# CubeNode.net
KiCad netlist of a schematic drawn in Altium Designer
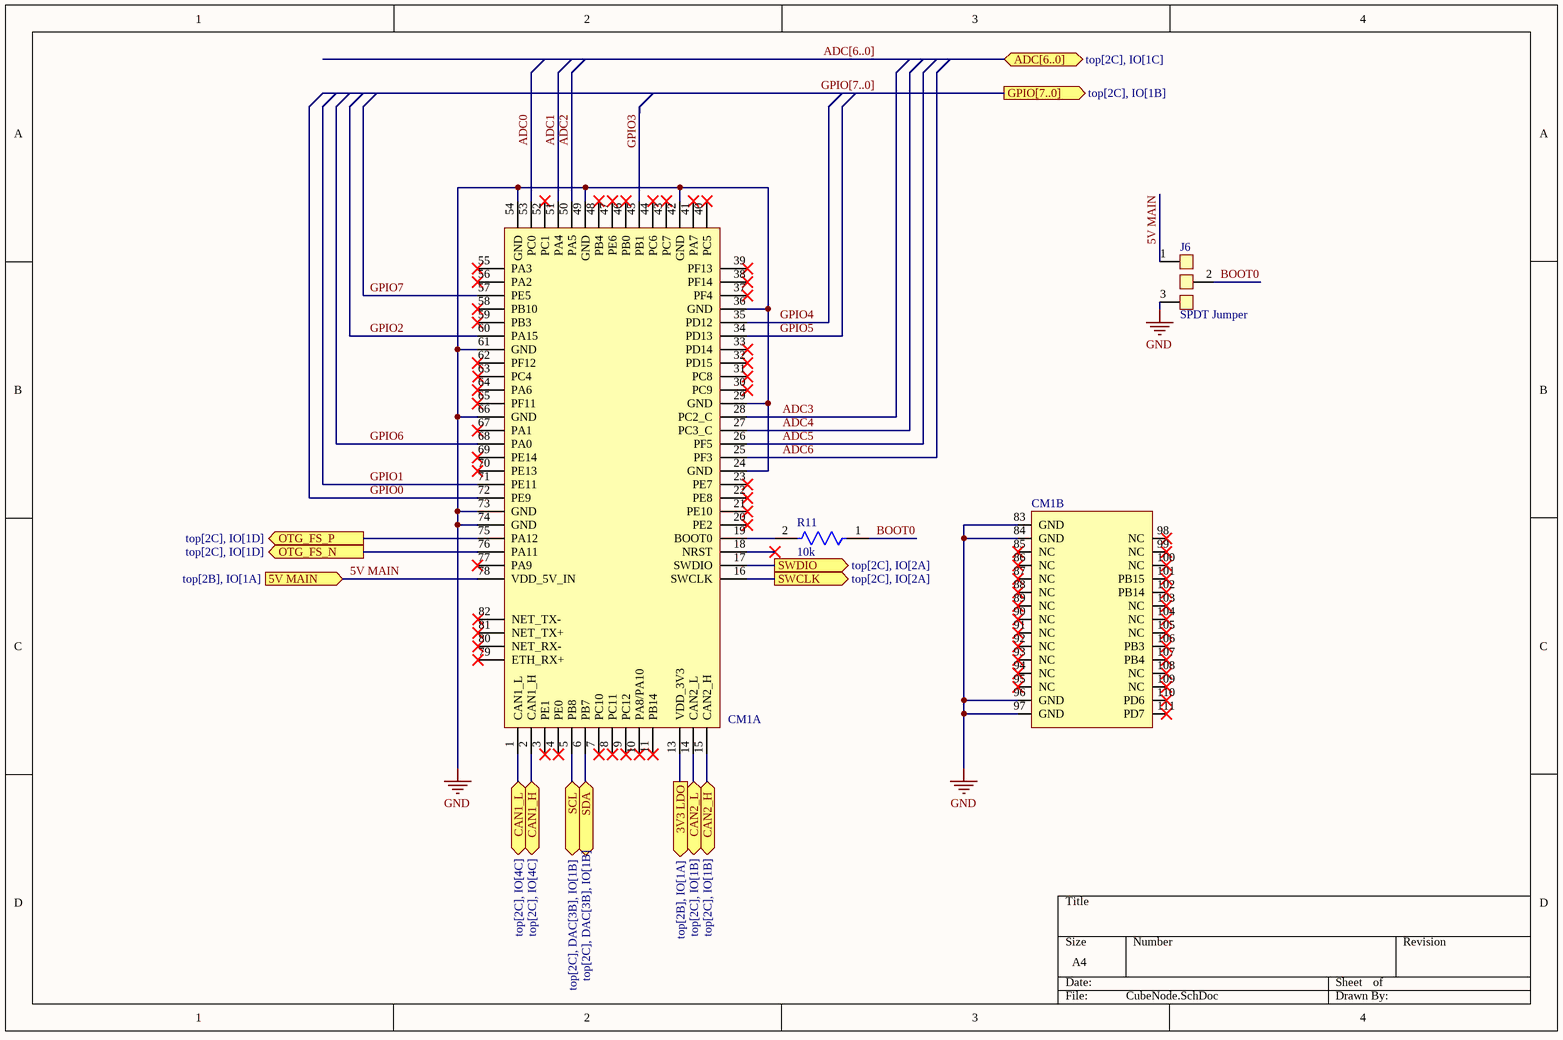
[diagram p0: CubeNode.SchDoc]

(export (version "E")
  (design (tool "Eeschema 10.0.6"))
  (components
    (comp (ref "CM1")
      (value "CUBENODE_FOOTPRINT")
      (footprint "CubeNode Footprint:CubeNode")
      (libsource (lib "CubeNode Footprint") (part "CubeNode Footprint"))
    )
    (comp (ref "J6")
      (value "SPDT Jumper")
      (footprint "SPDT Jumper")
      (libsource (lib "jumpers") (part "SPDT Jumper"))
    )
    (comp (ref "R11")
      (value "10k")
      (footprint "FP-AF0603-MFG")
      (description "Anti-Sulfurated Chip Resistors Automotive Grade 10kΩ 1% 100ppm/°C 0603")
      (libsource (lib "Altium Content Vault") (part "1029c3af85768c4190bb7ad29bc67b5"))
    )
  )
  (nets
    (net (code "1") (name "/3V3 LDO") (class "Default")
      (node (ref "CM1") (pin "13") (pinfunction "VDD_3V3_13") (pintype "passive"))
    )
    (net (code "2") (name "/5V MAIN") (class "Default")
      (node (ref "CM1") (pin "78") (pinfunction "VDD_5V_IN_78") (pintype "passive"))
      (node (ref "J6") (pin "1") (pinfunction "1_1") (pintype "passive"))
    )
    (net (code "3") (name "/ADC0") (class "Default")
      (node (ref "CM1") (pin "53") (pinfunction "PC0_53") (pintype "passive"))
    )
    (net (code "4") (name "/ADC1") (class "Default")
      (node (ref "CM1") (pin "51") (pinfunction "PA4_51") (pintype "passive"))
    )
    (net (code "5") (name "/ADC2") (class "Default")
      (node (ref "CM1") (pin "50") (pinfunction "PA5_50") (pintype "passive"))
    )
    (net (code "6") (name "/ADC3") (class "Default")
      (node (ref "CM1") (pin "28") (pinfunction "PC2_C_28") (pintype "passive"))
    )
    (net (code "7") (name "/ADC4") (class "Default")
      (node (ref "CM1") (pin "27") (pinfunction "PC3_C_27") (pintype "passive"))
    )
    (net (code "8") (name "/ADC5") (class "Default")
      (node (ref "CM1") (pin "26") (pinfunction "PF5_26") (pintype "passive"))
    )
    (net (code "9") (name "/ADC6") (class "Default")
      (node (ref "CM1") (pin "25") (pinfunction "PF3_25") (pintype "passive"))
    )
    (net (code "11") (name "/BOOT0") (class "Default")
      (node (ref "J6") (pin "2") (pinfunction "2_2") (pintype "passive"))
      (node (ref "R11") (pin "1") (pinfunction "1_1") (pintype "passive"))
    )
    (net (code "12") (name "/CAN1_H") (class "Default")
      (node (ref "CM1") (pin "2") (pinfunction "CAN1_H_2") (pintype "passive"))
    )
    (net (code "13") (name "/CAN1_L") (class "Default")
      (node (ref "CM1") (pin "1") (pinfunction "CAN1_L_1") (pintype "passive"))
    )
    (net (code "14") (name "/CAN2_H") (class "Default")
      (node (ref "CM1") (pin "15") (pinfunction "CAN2_H_15") (pintype "passive"))
    )
    (net (code "15") (name "/CAN2_L") (class "Default")
      (node (ref "CM1") (pin "14") (pinfunction "CAN2_L_14") (pintype "passive"))
    )
    (net (code "16") (name "/GPIO0") (class "Default")
      (node (ref "CM1") (pin "72") (pinfunction "PE9_72") (pintype "passive"))
    )
    (net (code "17") (name "/GPIO1") (class "Default")
      (node (ref "CM1") (pin "71") (pinfunction "PE11_71") (pintype "passive"))
    )
    (net (code "18") (name "/GPIO2") (class "Default")
      (node (ref "CM1") (pin "60") (pinfunction "PA15_60") (pintype "passive"))
    )
    (net (code "19") (name "/GPIO3") (class "Default")
      (node (ref "CM1") (pin "45") (pinfunction "PB1_45") (pintype "passive"))
    )
    (net (code "20") (name "/GPIO4") (class "Default")
      (node (ref "CM1") (pin "35") (pinfunction "PD12_35") (pintype "passive"))
    )
    (net (code "21") (name "/GPIO5") (class "Default")
      (node (ref "CM1") (pin "34") (pinfunction "PD13_34") (pintype "passive"))
    )
    (net (code "22") (name "/GPIO6") (class "Default")
      (node (ref "CM1") (pin "68") (pinfunction "PA0_68") (pintype "passive"))
    )
    (net (code "23") (name "/GPIO7") (class "Default")
      (node (ref "CM1") (pin "57") (pinfunction "PE5_57") (pintype "passive"))
    )
    (net (code "25") (name "/OTG_FS_N") (class "Default")
      (node (ref "CM1") (pin "76") (pinfunction "PA11_76") (pintype "passive"))
    )
    (net (code "26") (name "/OTG_FS_P") (class "Default")
      (node (ref "CM1") (pin "75") (pinfunction "PA12_75") (pintype "passive"))
    )
    (net (code "27") (name "/SCL") (class "Default")
      (node (ref "CM1") (pin "5") (pinfunction "PB8_5") (pintype "passive"))
    )
    (net (code "28") (name "/SDA") (class "Default")
      (node (ref "CM1") (pin "6") (pinfunction "PB7_6") (pintype "passive"))
    )
    (net (code "29") (name "/SWCLK") (class "Default")
      (node (ref "CM1") (pin "16") (pinfunction "SWCLK_16") (pintype "passive"))
    )
    (net (code "30") (name "/SWDIO") (class "Default")
      (node (ref "CM1") (pin "17") (pinfunction "SWDIO_17") (pintype "passive"))
    )
    (net (code "31") (name "GND") (class "Default")
      (node (ref "CM1") (pin "24") (pinfunction "GND_24") (pintype "passive"))
      (node (ref "CM1") (pin "29") (pinfunction "GND_29") (pintype "passive"))
      (node (ref "CM1") (pin "36") (pinfunction "GND_36") (pintype "passive"))
      (node (ref "CM1") (pin "42") (pinfunction "GND_42") (pintype "passive"))
      (node (ref "CM1") (pin "49") (pinfunction "GND_49") (pintype "passive"))
      (node (ref "CM1") (pin "54") (pinfunction "GND_54") (pintype "passive"))
      (node (ref "CM1") (pin "61") (pinfunction "GND_61") (pintype "passive"))
      (node (ref "CM1") (pin "66") (pinfunction "GND_66") (pintype "passive"))
      (node (ref "CM1") (pin "73") (pinfunction "GND_73") (pintype "passive"))
      (node (ref "CM1") (pin "74") (pinfunction "GND_74") (pintype "passive"))
      (node (ref "CM1") (pin "83") (pinfunction "GND_83") (pintype "passive"))
      (node (ref "CM1") (pin "84") (pinfunction "GND_84") (pintype "passive"))
      (node (ref "CM1") (pin "96") (pinfunction "GND_96") (pintype "passive"))
      (node (ref "CM1") (pin "97") (pinfunction "GND_97") (pintype "passive"))
      (node (ref "J6") (pin "3") (pinfunction "3_3") (pintype "passive"))
    )
    (net (code "32") (name "Net-(CM1A-BOOT0)") (class "Default")
      (node (ref "CM1") (pin "19") (pinfunction "BOOT0_19") (pintype "passive"))
      (node (ref "R11") (pin "2") (pinfunction "2_2") (pintype "passive"))
    )
    (net (code "33") (name "unconnected-(CM1A-ETH_RX+-Pad79)") (class "Default")
      (node (ref "CM1") (pin "79") (pinfunction "ETH_RX+_79") (pintype "passive+no_connect"))
    )
    (net (code "34") (name "unconnected-(CM1A-NET_RX--Pad80)") (class "Default")
      (node (ref "CM1") (pin "80") (pinfunction "NET_RX-_80") (pintype "passive+no_connect"))
    )
    (net (code "35") (name "unconnected-(CM1A-NET_TX+-Pad81)") (class "Default")
      (node (ref "CM1") (pin "81") (pinfunction "NET_TX+_81") (pintype "passive+no_connect"))
    )
    (net (code "36") (name "unconnected-(CM1A-NET_TX--Pad82)") (class "Default")
      (node (ref "CM1") (pin "82") (pinfunction "NET_TX-_82") (pintype "passive+no_connect"))
    )
    (net (code "37") (name "unconnected-(CM1A-NRST-Pad18)") (class "Default")
      (node (ref "CM1") (pin "18") (pinfunction "NRST_18") (pintype "passive+no_connect"))
    )
    (net (code "38") (name "unconnected-(CM1A-PA1-Pad67)") (class "Default")
      (node (ref "CM1") (pin "67") (pinfunction "PA1_67") (pintype "passive+no_connect"))
    )
    (net (code "39") (name "unconnected-(CM1A-PA2-Pad56)") (class "Default")
      (node (ref "CM1") (pin "56") (pinfunction "PA2_56") (pintype "passive+no_connect"))
    )
    (net (code "40") (name "unconnected-(CM1A-PA3-Pad55)") (class "Default")
      (node (ref "CM1") (pin "55") (pinfunction "PA3_55") (pintype "passive+no_connect"))
    )
    (net (code "41") (name "unconnected-(CM1A-PA6-Pad64)") (class "Default")
      (node (ref "CM1") (pin "64") (pinfunction "PA6_64") (pintype "passive+no_connect"))
    )
    (net (code "42") (name "unconnected-(CM1A-PA7-Pad41)") (class "Default")
      (node (ref "CM1") (pin "41") (pinfunction "PA7_41") (pintype "passive+no_connect"))
    )
    (net (code "43") (name "unconnected-(CM1A-PA8{slash}PA10-Pad10)") (class "Default")
      (node (ref "CM1") (pin "10") (pinfunction "PA8/PA10_10") (pintype "passive+no_connect"))
    )
    (net (code "44") (name "unconnected-(CM1A-PA9-Pad77)") (class "Default")
      (node (ref "CM1") (pin "77") (pinfunction "PA9_77") (pintype "passive+no_connect"))
    )
    (net (code "45") (name "unconnected-(CM1A-PB0-Pad46)") (class "Default")
      (node (ref "CM1") (pin "46") (pinfunction "PB0_46") (pintype "passive+no_connect"))
    )
    (net (code "46") (name "unconnected-(CM1A-PB3-Pad59)") (class "Default")
      (node (ref "CM1") (pin "59") (pinfunction "PB3_59") (pintype "passive+no_connect"))
    )
    (net (code "47") (name "unconnected-(CM1A-PB4-Pad48)") (class "Default")
      (node (ref "CM1") (pin "48") (pinfunction "PB4_48") (pintype "passive+no_connect"))
    )
    (net (code "48") (name "unconnected-(CM1A-PB10-Pad58)") (class "Default")
      (node (ref "CM1") (pin "58") (pinfunction "PB10_58") (pintype "passive+no_connect"))
    )
    (net (code "49") (name "unconnected-(CM1A-PB14-Pad11)") (class "Default")
      (node (ref "CM1") (pin "11") (pinfunction "PB14_11") (pintype "passive+no_connect"))
    )
    (net (code "50") (name "unconnected-(CM1A-PC1-Pad52)") (class "Default")
      (node (ref "CM1") (pin "52") (pinfunction "PC1_52") (pintype "passive+no_connect"))
    )
    (net (code "51") (name "unconnected-(CM1A-PC4-Pad63)") (class "Default")
      (node (ref "CM1") (pin "63") (pinfunction "PC4_63") (pintype "passive"))
    )
    (net (code "52") (name "unconnected-(CM1A-PC5-Pad40)") (class "Default")
      (node (ref "CM1") (pin "40") (pinfunction "PC5_40") (pintype "passive+no_connect"))
    )
    (net (code "53") (name "unconnected-(CM1A-PC6-Pad44)") (class "Default")
      (node (ref "CM1") (pin "44") (pinfunction "PC6_44") (pintype "passive+no_connect"))
    )
    (net (code "54") (name "unconnected-(CM1A-PC7-Pad43)") (class "Default")
      (node (ref "CM1") (pin "43") (pinfunction "PC7_43") (pintype "passive+no_connect"))
    )
    (net (code "55") (name "unconnected-(CM1A-PC8-Pad31)") (class "Default")
      (node (ref "CM1") (pin "31") (pinfunction "PC8_31") (pintype "passive+no_connect"))
    )
    (net (code "56") (name "unconnected-(CM1A-PC9-Pad30)") (class "Default")
      (node (ref "CM1") (pin "30") (pinfunction "PC9_30") (pintype "passive+no_connect"))
    )
    (net (code "57") (name "unconnected-(CM1A-PC10-Pad7)") (class "Default")
      (node (ref "CM1") (pin "7") (pinfunction "PC10_7") (pintype "passive+no_connect"))
    )
    (net (code "58") (name "unconnected-(CM1A-PC11-Pad8)") (class "Default")
      (node (ref "CM1") (pin "8") (pinfunction "PC11_8") (pintype "passive+no_connect"))
    )
    (net (code "59") (name "unconnected-(CM1A-PC12-Pad9)") (class "Default")
      (node (ref "CM1") (pin "9") (pinfunction "PC12_9") (pintype "passive+no_connect"))
    )
    (net (code "60") (name "unconnected-(CM1A-PD14-Pad33)") (class "Default")
      (node (ref "CM1") (pin "33") (pinfunction "PD14_33") (pintype "passive+no_connect"))
    )
    (net (code "61") (name "unconnected-(CM1A-PD15-Pad32)") (class "Default")
      (node (ref "CM1") (pin "32") (pinfunction "PD15_32") (pintype "passive+no_connect"))
    )
    (net (code "62") (name "unconnected-(CM1A-PE0-Pad4)") (class "Default")
      (node (ref "CM1") (pin "4") (pinfunction "PE0_4") (pintype "passive+no_connect"))
    )
    (net (code "63") (name "unconnected-(CM1A-PE1-Pad3)") (class "Default")
      (node (ref "CM1") (pin "3") (pinfunction "PE1_3") (pintype "passive+no_connect"))
    )
    (net (code "64") (name "unconnected-(CM1A-PE2-Pad20)") (class "Default")
      (node (ref "CM1") (pin "20") (pinfunction "PE2_20") (pintype "passive+no_connect"))
    )
    (net (code "65") (name "unconnected-(CM1A-PE6-Pad47)") (class "Default")
      (node (ref "CM1") (pin "47") (pinfunction "PE6_47") (pintype "passive+no_connect"))
    )
    (net (code "66") (name "unconnected-(CM1A-PE7-Pad23)") (class "Default")
      (node (ref "CM1") (pin "23") (pinfunction "PE7_23") (pintype "passive+no_connect"))
    )
    (net (code "67") (name "unconnected-(CM1A-PE8-Pad22)") (class "Default")
      (node (ref "CM1") (pin "22") (pinfunction "PE8_22") (pintype "passive+no_connect"))
    )
    (net (code "68") (name "unconnected-(CM1A-PE10-Pad21)") (class "Default")
      (node (ref "CM1") (pin "21") (pinfunction "PE10_21") (pintype "passive+no_connect"))
    )
    (net (code "69") (name "unconnected-(CM1A-PE13-Pad70)") (class "Default")
      (node (ref "CM1") (pin "70") (pinfunction "PE13_70") (pintype "passive+no_connect"))
    )
    (net (code "70") (name "unconnected-(CM1A-PE14-Pad69)") (class "Default")
      (node (ref "CM1") (pin "69") (pinfunction "PE14_69") (pintype "passive+no_connect"))
    )
    (net (code "71") (name "unconnected-(CM1A-PF4-Pad37)") (class "Default")
      (node (ref "CM1") (pin "37") (pinfunction "PF4_37") (pintype "passive+no_connect"))
    )
    (net (code "72") (name "unconnected-(CM1A-PF11-Pad65)") (class "Default")
      (node (ref "CM1") (pin "65") (pinfunction "PF11_65") (pintype "passive+no_connect"))
    )
    (net (code "73") (name "unconnected-(CM1A-PF12-Pad62)") (class "Default")
      (node (ref "CM1") (pin "62") (pinfunction "PF12_62") (pintype "passive+no_connect"))
    )
    (net (code "74") (name "unconnected-(CM1A-PF13-Pad39)") (class "Default")
      (node (ref "CM1") (pin "39") (pinfunction "PF13_39") (pintype "passive+no_connect"))
    )
    (net (code "75") (name "unconnected-(CM1A-PF14-Pad38)") (class "Default")
      (node (ref "CM1") (pin "38") (pinfunction "PF14_38") (pintype "passive+no_connect"))
    )
    (net (code "76") (name "unconnected-(CM1B-NC-Pad85)") (class "Default")
      (node (ref "CM1") (pin "85") (pinfunction "NC_85") (pintype "passive+no_connect"))
    )
    (net (code "77") (name "unconnected-(CM1B-NC-Pad86)") (class "Default")
      (node (ref "CM1") (pin "86") (pinfunction "NC_86") (pintype "passive+no_connect"))
    )
    (net (code "78") (name "unconnected-(CM1B-NC-Pad87)") (class "Default")
      (node (ref "CM1") (pin "87") (pinfunction "NC_87") (pintype "passive+no_connect"))
    )
    (net (code "79") (name "unconnected-(CM1B-NC-Pad88)") (class "Default")
      (node (ref "CM1") (pin "88") (pinfunction "NC_88") (pintype "passive+no_connect"))
    )
    (net (code "80") (name "unconnected-(CM1B-NC-Pad89)") (class "Default")
      (node (ref "CM1") (pin "89") (pinfunction "NC_89") (pintype "passive+no_connect"))
    )
    (net (code "81") (name "unconnected-(CM1B-NC-Pad90)") (class "Default")
      (node (ref "CM1") (pin "90") (pinfunction "NC_90") (pintype "passive+no_connect"))
    )
    (net (code "82") (name "unconnected-(CM1B-NC-Pad91)") (class "Default")
      (node (ref "CM1") (pin "91") (pinfunction "NC_91") (pintype "passive+no_connect"))
    )
    (net (code "83") (name "unconnected-(CM1B-NC-Pad92)") (class "Default")
      (node (ref "CM1") (pin "92") (pinfunction "NC_92") (pintype "passive+no_connect"))
    )
    (net (code "84") (name "unconnected-(CM1B-NC-Pad93)") (class "Default")
      (node (ref "CM1") (pin "93") (pinfunction "NC_93") (pintype "passive+no_connect"))
    )
    (net (code "85") (name "unconnected-(CM1B-NC-Pad94)") (class "Default")
      (node (ref "CM1") (pin "94") (pinfunction "NC_94") (pintype "passive+no_connect"))
    )
    (net (code "86") (name "unconnected-(CM1B-NC-Pad95)") (class "Default")
      (node (ref "CM1") (pin "95") (pinfunction "NC_95") (pintype "passive+no_connect"))
    )
    (net (code "87") (name "unconnected-(CM1B-NC-Pad98)") (class "Default")
      (node (ref "CM1") (pin "98") (pinfunction "NC_98") (pintype "passive+no_connect"))
    )
    (net (code "88") (name "unconnected-(CM1B-NC-Pad99)") (class "Default")
      (node (ref "CM1") (pin "99") (pinfunction "NC_99") (pintype "passive+no_connect"))
    )
    (net (code "89") (name "unconnected-(CM1B-NC-Pad100)") (class "Default")
      (node (ref "CM1") (pin "100") (pinfunction "NC_100") (pintype "passive+no_connect"))
    )
    (net (code "90") (name "unconnected-(CM1B-NC-Pad103)") (class "Default")
      (node (ref "CM1") (pin "103") (pinfunction "NC_103") (pintype "passive+no_connect"))
    )
    (net (code "91") (name "unconnected-(CM1B-NC-Pad104)") (class "Default")
      (node (ref "CM1") (pin "104") (pinfunction "NC_104") (pintype "passive+no_connect"))
    )
    (net (code "92") (name "unconnected-(CM1B-NC-Pad105)") (class "Default")
      (node (ref "CM1") (pin "105") (pinfunction "NC_105") (pintype "passive+no_connect"))
    )
    (net (code "93") (name "unconnected-(CM1B-NC-Pad108)") (class "Default")
      (node (ref "CM1") (pin "108") (pinfunction "NC_108") (pintype "passive+no_connect"))
    )
    (net (code "94") (name "unconnected-(CM1B-NC-Pad109)") (class "Default")
      (node (ref "CM1") (pin "109") (pinfunction "NC_109") (pintype "passive+no_connect"))
    )
    (net (code "95") (name "unconnected-(CM1B-PB3-Pad106)") (class "Default")
      (node (ref "CM1") (pin "106") (pinfunction "PB3_106") (pintype "passive+no_connect"))
    )
    (net (code "96") (name "unconnected-(CM1B-PB4-Pad107)") (class "Default")
      (node (ref "CM1") (pin "107") (pinfunction "PB4_107") (pintype "passive+no_connect"))
    )
    (net (code "97") (name "unconnected-(CM1B-PB14-Pad102)") (class "Default")
      (node (ref "CM1") (pin "102") (pinfunction "PB14_102") (pintype "passive+no_connect"))
    )
    (net (code "98") (name "unconnected-(CM1B-PB15-Pad101)") (class "Default")
      (node (ref "CM1") (pin "101") (pinfunction "PB15_101") (pintype "passive+no_connect"))
    )
    (net (code "99") (name "unconnected-(CM1B-PD6-Pad110)") (class "Default")
      (node (ref "CM1") (pin "110") (pinfunction "PD6_110") (pintype "passive+no_connect"))
    )
    (net (code "100") (name "unconnected-(CM1B-PD7-Pad111)") (class "Default")
      (node (ref "CM1") (pin "111") (pinfunction "PD7_111") (pintype "passive+no_connect"))
    )
  )
)
